# SENSORS.net
KiCad netlist of a schematic drawn in Altium Designer
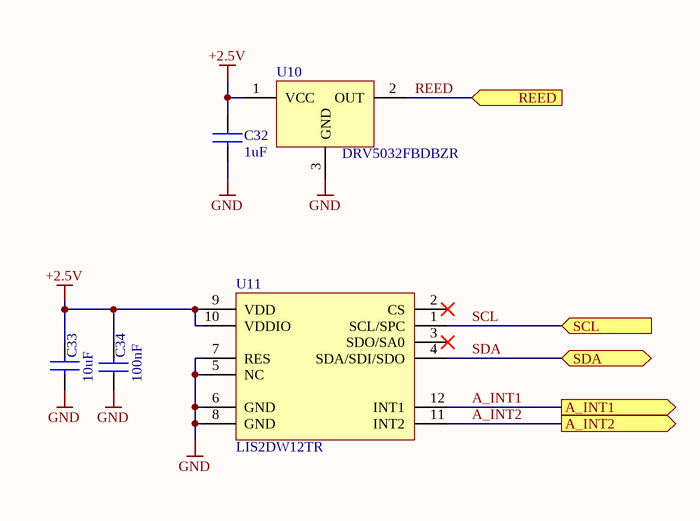
[diagram p0: SENSORS.SchDoc]

(export (version "E")
  (design (tool "Eeschema 10.0.6"))
  (components
    (comp (ref "C32")
      (value "1uF")
      (footprint "CAP0402")
      (description "CAP CER 1UF 10V 20% X5R 0402")
      (fields
        (field (name "MANUFACTURER") "Murata")
        (field (name "MANUFACTURER PART NUMBER") "GRM155R61A105ME15D")
      )
      (libsource (lib "Passive") (part "C - 1uF/0402"))
    )
    (comp (ref "C33")
      (value "10uF")
      (footprint "CAP0603")
      (description "Cap Ceramic 10uF 10V X5R 10% SMD 0603 85C Paper T/R")
      (fields
        (field (name "MANUFACTURER") "Samsung")
        (field (name "MANUFACTURER PART NUMBER") "CL10A106KP8NNNC")
      )
      (libsource (lib "Passive") (part "C - 10uF/10V"))
    )
    (comp (ref "C34")
      (value "100nF")
      (footprint "CAP0402")
      (fields
        (field (name "MANUFACTURER") "Multicomp")
        (field (name "MANUFACTURER PART NUMBER") "MC0402X104J160CT")
        (field (name "TOLERANCE") "5%")
      )
      (libsource (lib "Passive") (part "C - 100nF/0402"))
    )
    (comp (ref "U10")
      (value "DRV5032FBDBZR")
      (footprint "SOT23-3AL")
      (description "Board Mount Hall Effect/Magnetic Sensors LP HALL 32FBDBZR")
      (fields
        (field (name "MANUFACTURER") "TDK InvenSense")
        (field (name "MANUFACTURER PART NUMBER") "MPU-9250")
      )
      (libsource (lib "Active") (part "SEN - DRV5032FBDBZR"))
    )
    (comp (ref "U11")
      (value "LIS2DW12TR")
      (footprint "LGA-12")
      (description "MEMS Accelerometer, Digital, X, Y, Z, ± 2g, ± 4g, ± 8g, ± 16g, 1.62 V, 3.6 V")
      (fields
        (field (name "MANUFACTURER") "TDK InvenSense")
        (field (name "MANUFACTURER PART NUMBER") "MPU-9250")
      )
      (libsource (lib "Active") (part "SEN - LIS2DW12TR"))
    )
  )
  (nets
    (net (code "1") (name "+2.5V") (class "Default")
      (node (ref "C32") (pin "1") (pinfunction "1_1") (pintype "passive"))
      (node (ref "C33") (pin "1") (pinfunction "1_1") (pintype "passive"))
      (node (ref "C34") (pin "2") (pinfunction "2_2") (pintype "passive"))
      (node (ref "U10") (pin "1") (pinfunction "VCC_1") (pintype "passive"))
      (node (ref "U11") (pin "10") (pinfunction "VDDIO_10") (pintype "passive"))
      (node (ref "U11") (pin "9") (pinfunction "VDD_9") (pintype "passive"))
    )
    (net (code "2") (name "/A_INT1") (class "Default")
      (node (ref "U11") (pin "12") (pinfunction "INT1_12") (pintype "passive"))
    )
    (net (code "3") (name "/A_INT2") (class "Default")
      (node (ref "U11") (pin "11") (pinfunction "INT2_11") (pintype "passive"))
    )
    (net (code "4") (name "/REED") (class "Default")
      (node (ref "U10") (pin "2") (pinfunction "OUT_2") (pintype "passive"))
    )
    (net (code "5") (name "/SCL") (class "Default")
      (node (ref "U11") (pin "1") (pinfunction "SCL/SPC_1") (pintype "passive"))
    )
    (net (code "6") (name "/SDA") (class "Default")
      (node (ref "U11") (pin "4") (pinfunction "SDA/SDI/SDO_4") (pintype "passive"))
    )
    (net (code "7") (name "GND") (class "Default")
      (node (ref "C32") (pin "2") (pinfunction "2_2") (pintype "passive"))
      (node (ref "C33") (pin "2") (pinfunction "2_2") (pintype "passive"))
      (node (ref "C34") (pin "1") (pinfunction "1_1") (pintype "passive"))
      (node (ref "U10") (pin "3") (pinfunction "GND_3") (pintype "passive"))
      (node (ref "U11") (pin "5") (pinfunction "NC_5") (pintype "passive"))
      (node (ref "U11") (pin "6") (pinfunction "GND_6") (pintype "passive"))
      (node (ref "U11") (pin "7") (pinfunction "RES_7") (pintype "passive"))
      (node (ref "U11") (pin "8") (pinfunction "GND_8") (pintype "passive"))
    )
    (net (code "8") (name "unconnected-(U11-CS-Pad2)") (class "Default")
      (node (ref "U11") (pin "2") (pinfunction "CS_2") (pintype "passive+no_connect"))
    )
    (net (code "9") (name "unconnected-(U11-SDO{slash}SA0-Pad3)") (class "Default")
      (node (ref "U11") (pin "3") (pinfunction "SDO/SA0_3") (pintype "passive+no_connect"))
    )
  )
)
